# h_bridge_driver.net
KiCad netlist of a schematic drawn in EAGLE
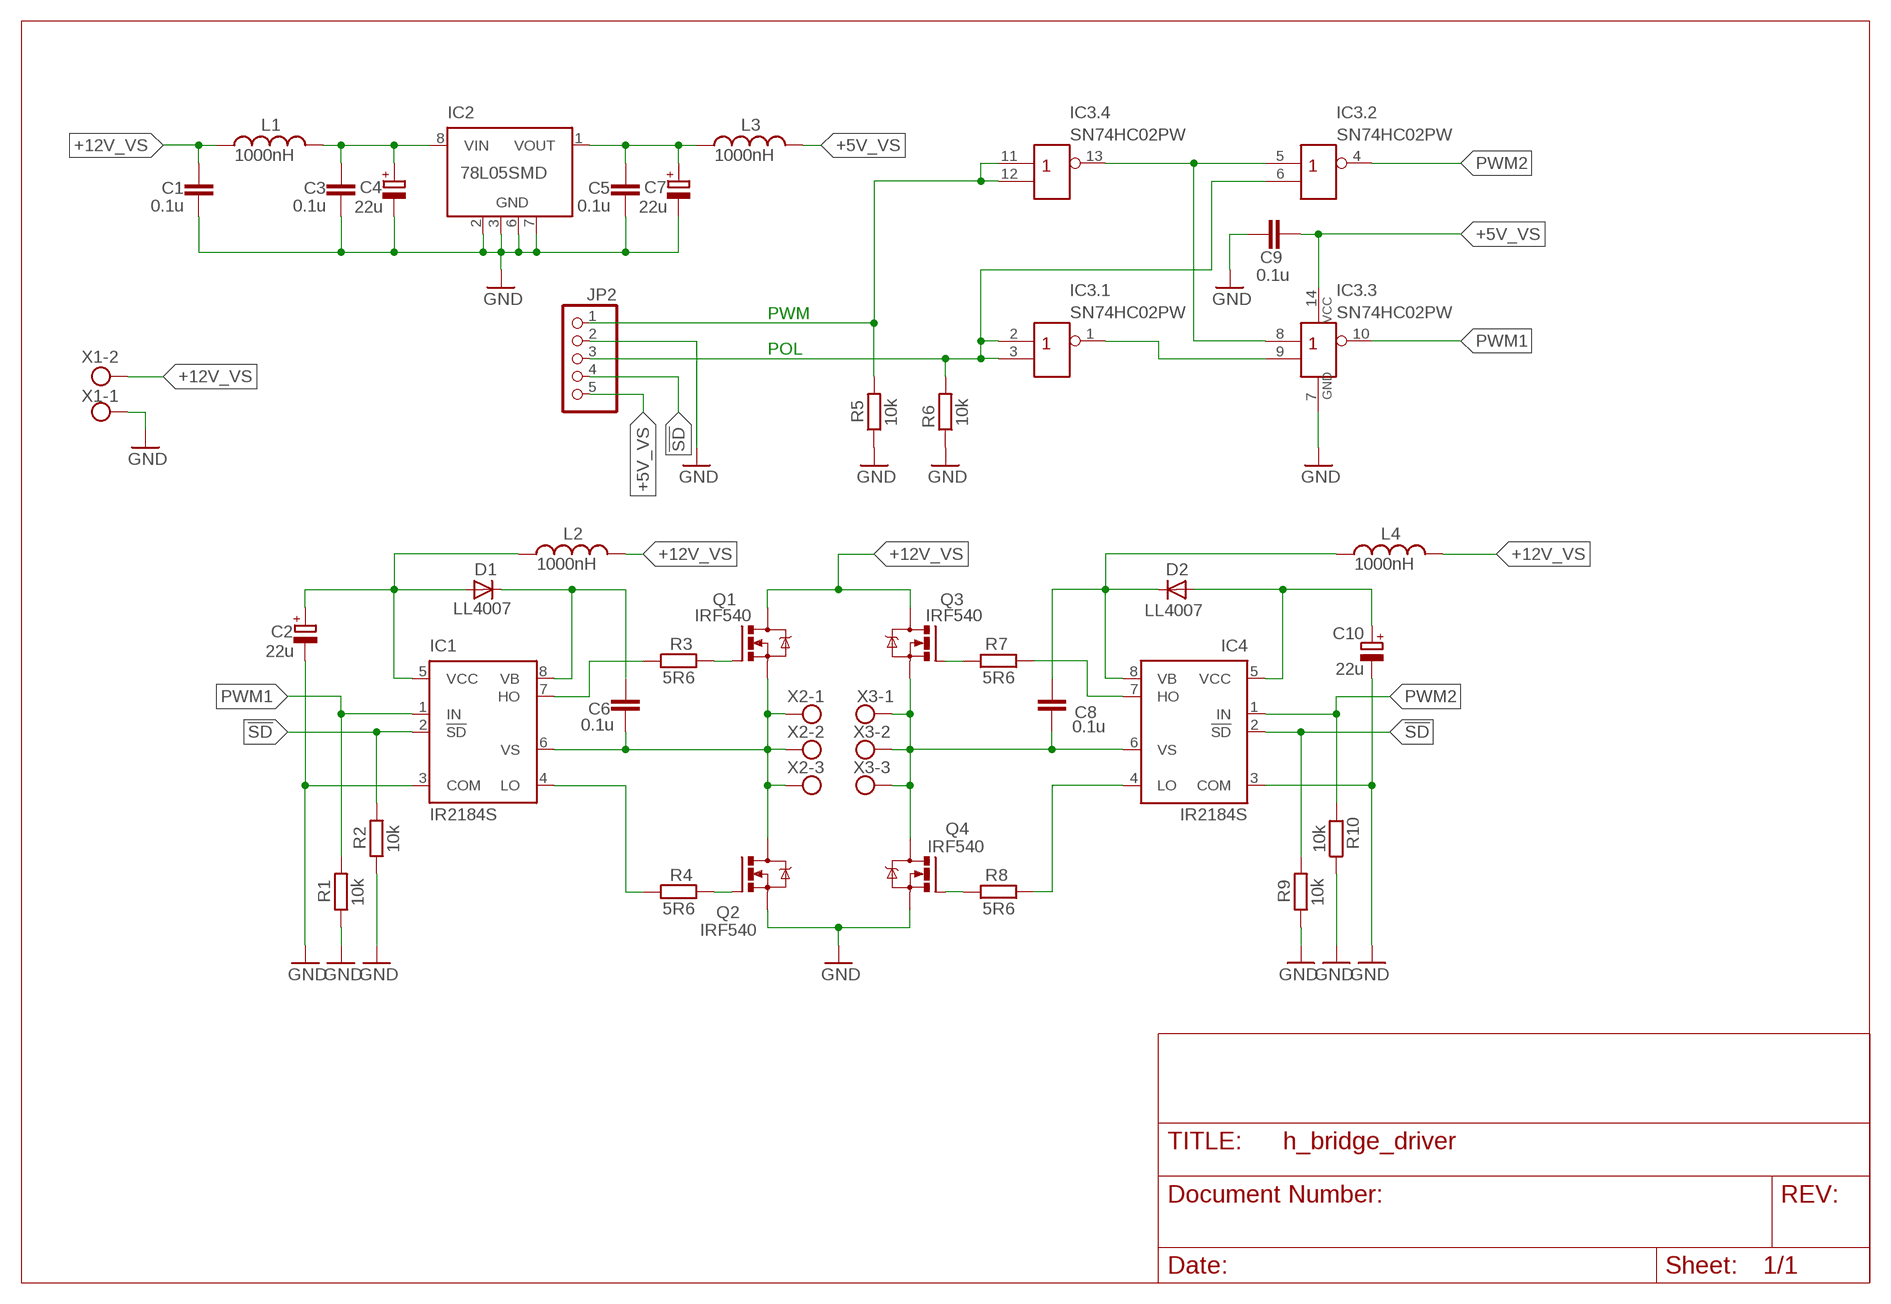
[diagram p0: schematic, sheet 1]

(export (version "E")
  (design (tool "Eeschema 10.0.6"))
  (components
    (comp (ref "C1")
      (value "0.1u")
      (footprint "eagle-import:C1206")
      (libsource (lib "eagle-import") (part "C-EUC1206"))
    )
    (comp (ref "C2")
      (value "22u")
      (footprint "eagle-import:SMC_C")
      (libsource (lib "eagle-import") (part "CPOL-EUSMCC"))
    )
    (comp (ref "C3")
      (value "0.1u")
      (footprint "eagle-import:C1206")
      (libsource (lib "eagle-import") (part "C-EUC1206"))
    )
    (comp (ref "C4")
      (value "22u")
      (footprint "eagle-import:SMC_C")
      (libsource (lib "eagle-import") (part "CPOL-EUSMCC"))
    )
    (comp (ref "C5")
      (value "0.1u")
      (footprint "eagle-import:C1206")
      (libsource (lib "eagle-import") (part "C-EUC1206"))
    )
    (comp (ref "C6")
      (value "0.1u")
      (footprint "eagle-import:C1206")
      (libsource (lib "eagle-import") (part "C-EUC1206"))
    )
    (comp (ref "C7")
      (value "22u")
      (footprint "eagle-import:SMC_C")
      (libsource (lib "eagle-import") (part "CPOL-EUSMCC"))
    )
    (comp (ref "C8")
      (value "0.1u")
      (footprint "eagle-import:C1206")
      (libsource (lib "eagle-import") (part "C-EUC1206"))
    )
    (comp (ref "C9")
      (value "0.1u")
      (footprint "eagle-import:C1206")
      (libsource (lib "eagle-import") (part "C-EUC1206"))
    )
    (comp (ref "C10")
      (value "22u")
      (footprint "eagle-import:SMC_C")
      (libsource (lib "eagle-import") (part "CPOL-EUSMCC"))
    )
    (comp (ref "D1")
      (value "LL4007")
      (footprint "eagle-import:MINIMELF")
      (libsource (lib "eagle-import") (part "DIODE-MINIMELF"))
    )
    (comp (ref "D2")
      (value "LL4007")
      (footprint "eagle-import:MINIMELF")
      (libsource (lib "eagle-import") (part "DIODE-MINIMELF"))
    )
    (comp (ref "IC1")
      (value "IR2184S")
      (footprint "eagle-import:SO08")
      (fields (field (name "MF") "INTERNATIONAL RECTIFIER(IR)") (field (name "MPN") "IR2184"))
      (libsource (lib "eagle-import") (part "IR2184S"))
    )
    (comp (ref "IC2")
      (value "78L05SMD")
      (footprint "eagle-import:SO08")
      (libsource (lib "eagle-import") (part "78LSMD05"))
    )
    (comp (ref "IC3")
      (value "SN74HC02PW")
      (footprint "eagle-import:SO14")
      (libsource (lib "eagle-import") (part "7402D"))
    )
    (comp (ref "IC4")
      (value "IR2184S")
      (footprint "eagle-import:SO08")
      (fields (field (name "MF") "INTERNATIONAL RECTIFIER(IR)") (field (name "MPN") "IR2184"))
      (libsource (lib "eagle-import") (part "IR2184S"))
    )
    (comp (ref "JP2")
      (value "PINHD-1X55X2MM")
      (footprint "eagle-import:1_05X2MM")
      (libsource (lib "eagle-import") (part "PINHD-1X55X2MM"))
    )
    (comp (ref "L1")
      (value "1000nH")
      (footprint "eagle-import:L1812")
      (libsource (lib "eagle-import") (part "L-USL1812"))
    )
    (comp (ref "L2")
      (value "1000nH")
      (footprint "eagle-import:L1812")
      (libsource (lib "eagle-import") (part "L-USL1812"))
    )
    (comp (ref "L3")
      (value "1000nH")
      (footprint "eagle-import:L1812")
      (libsource (lib "eagle-import") (part "L-USL1812"))
    )
    (comp (ref "L4")
      (value "1000nH")
      (footprint "eagle-import:L1812")
      (libsource (lib "eagle-import") (part "L-USL1812"))
    )
    (comp (ref "Q1")
      (value "IRF540")
      (footprint "eagle-import:TO220BV")
      (libsource (lib "eagle-import") (part "IRF540"))
    )
    (comp (ref "Q2")
      (value "IRF540")
      (footprint "eagle-import:TO220BV")
      (libsource (lib "eagle-import") (part "IRF540"))
    )
    (comp (ref "Q3")
      (value "IRF540")
      (footprint "eagle-import:TO220BV")
      (libsource (lib "eagle-import") (part "IRF540"))
    )
    (comp (ref "Q4")
      (value "IRF540")
      (footprint "eagle-import:TO220BV")
      (libsource (lib "eagle-import") (part "IRF540"))
    )
    (comp (ref "R1")
      (value "10k")
      (footprint "eagle-import:R0603")
      (libsource (lib "eagle-import") (part "R-EU_R0603"))
    )
    (comp (ref "R2")
      (value "10k")
      (footprint "eagle-import:R0603")
      (libsource (lib "eagle-import") (part "R-EU_R0603"))
    )
    (comp (ref "R3")
      (value "5R6")
      (footprint "eagle-import:R0603")
      (libsource (lib "eagle-import") (part "R-EU_R0603"))
    )
    (comp (ref "R4")
      (value "5R6")
      (footprint "eagle-import:R0603")
      (libsource (lib "eagle-import") (part "R-EU_R0603"))
    )
    (comp (ref "R5")
      (value "10k")
      (footprint "eagle-import:R0603")
      (libsource (lib "eagle-import") (part "R-EU_R0603"))
    )
    (comp (ref "R6")
      (value "10k")
      (footprint "eagle-import:R0603")
      (libsource (lib "eagle-import") (part "R-EU_R0603"))
    )
    (comp (ref "R7")
      (value "5R6")
      (footprint "eagle-import:R0603")
      (libsource (lib "eagle-import") (part "R-EU_R0603"))
    )
    (comp (ref "R8")
      (value "5R6")
      (footprint "eagle-import:R0603")
      (libsource (lib "eagle-import") (part "R-EU_R0603"))
    )
    (comp (ref "R9")
      (value "10k")
      (footprint "eagle-import:R0603")
      (libsource (lib "eagle-import") (part "R-EU_R0603"))
    )
    (comp (ref "R10")
      (value "10k")
      (footprint "eagle-import:R0603")
      (libsource (lib "eagle-import") (part "R-EU_R0603"))
    )
    (comp (ref "X1")
      (value "MKDSN1,5/2-5,08")
      (footprint "eagle-import:MKDSN1,5_2-5,08")
      (libsource (lib "eagle-import") (part "MKDSN1,5/2-5,08"))
    )
    (comp (ref "X2")
      (value "MKDSN1,5/3-5,08")
      (footprint "eagle-import:MKDSN1,5_3-5,08")
      (libsource (lib "eagle-import") (part "MKDSN1,5/3-5,08"))
    )
    (comp (ref "X3")
      (value "MKDSN1,5/3-5,08")
      (footprint "eagle-import:MKDSN1,5_3-5,08")
      (libsource (lib "eagle-import") (part "MKDSN1,5/3-5,08"))
    )
  )
  (nets
    (net (code "1") (name "+5V_VS") (class "Default")
      (node (ref "C9") (pin "1") (pinfunction "1_1") (pintype "passive"))
      (node (ref "IC3") (pin "14") (pinfunction "VCC_14") (pintype "power_in"))
      (node (ref "JP2") (pin "5") (pinfunction "5_5") (pintype "passive"))
      (node (ref "L3") (pin "2") (pinfunction "2_2") (pintype "passive"))
    )
    (net (code "2") (name "+12V_VS") (class "Default")
      (node (ref "C1") (pin "1") (pinfunction "1_1") (pintype "passive"))
      (node (ref "L1") (pin "1") (pinfunction "1_1") (pintype "passive"))
      (node (ref "L2") (pin "2") (pinfunction "2_2") (pintype "passive"))
      (node (ref "L4") (pin "2") (pinfunction "2_2") (pintype "passive"))
      (node (ref "Q1") (pin "D") (pinfunction "D_D") (pintype "passive"))
      (node (ref "Q3") (pin "D") (pinfunction "D_D") (pintype "passive"))
      (node (ref "X1") (pin "2") (pinfunction "KL_2") (pintype "passive"))
    )
    (net (code "3") (name "/~{SD}") (class "Default")
      (node (ref "IC1") (pin "2") (pinfunction "~{SD}_2") (pintype "input"))
      (node (ref "IC4") (pin "2") (pinfunction "~{SD}_2") (pintype "input"))
      (node (ref "JP2") (pin "4") (pinfunction "4_4") (pintype "passive"))
      (node (ref "R2") (pin "2") (pinfunction "2_2") (pintype "passive"))
      (node (ref "R9") (pin "2") (pinfunction "2_2") (pintype "passive"))
    )
    (net (code "4") (name "GND") (class "Default")
      (node (ref "C1") (pin "2") (pinfunction "2_2") (pintype "passive"))
      (node (ref "C10") (pin "-") (pinfunction "-_-") (pintype "passive"))
      (node (ref "C2") (pin "-") (pinfunction "-_-") (pintype "passive"))
      (node (ref "C3") (pin "2") (pinfunction "2_2") (pintype "passive"))
      (node (ref "C4") (pin "-") (pinfunction "-_-") (pintype "passive"))
      (node (ref "C5") (pin "2") (pinfunction "2_2") (pintype "passive"))
      (node (ref "C7") (pin "-") (pinfunction "-_-") (pintype "passive"))
      (node (ref "C9") (pin "2") (pinfunction "2_2") (pintype "passive"))
      (node (ref "IC1") (pin "3") (pinfunction "COM_3") (pintype "power_in"))
      (node (ref "IC2") (pin "2") (pinfunction "GND_2") (pintype "power_in"))
      (node (ref "IC2") (pin "3") (pinfunction "GND_3") (pintype "power_in"))
      (node (ref "IC2") (pin "6") (pinfunction "GND_6") (pintype "power_in"))
      (node (ref "IC2") (pin "7") (pinfunction "GND_7") (pintype "power_in"))
      (node (ref "IC3") (pin "7") (pinfunction "GND_7") (pintype "power_in"))
      (node (ref "IC4") (pin "3") (pinfunction "COM_3") (pintype "power_in"))
      (node (ref "JP2") (pin "2") (pinfunction "2_2") (pintype "passive"))
      (node (ref "Q2") (pin "S") (pinfunction "S_S") (pintype "passive"))
      (node (ref "Q4") (pin "S") (pinfunction "S_S") (pintype "passive"))
      (node (ref "R1") (pin "1") (pinfunction "1_1") (pintype "passive"))
      (node (ref "R10") (pin "1") (pinfunction "1_1") (pintype "passive"))
      (node (ref "R2") (pin "1") (pinfunction "1_1") (pintype "passive"))
      (node (ref "R5") (pin "1") (pinfunction "1_1") (pintype "passive"))
      (node (ref "R6") (pin "1") (pinfunction "1_1") (pintype "passive"))
      (node (ref "R9") (pin "1") (pinfunction "1_1") (pintype "passive"))
      (node (ref "X1") (pin "1") (pinfunction "KL_1") (pintype "passive"))
    )
    (net (code "5") (name "Net-(IC1-HO)") (class "Default")
      (node (ref "IC1") (pin "7") (pinfunction "HO_7") (pintype "passive"))
      (node (ref "R3") (pin "1") (pinfunction "1_1") (pintype "passive"))
    )
    (net (code "6") (name "Net-(IC1-LO)") (class "Default")
      (node (ref "IC1") (pin "4") (pinfunction "LO_4") (pintype "output"))
      (node (ref "R4") (pin "1") (pinfunction "1_1") (pintype "passive"))
    )
    (net (code "7") (name "Net-(IC1-VB)") (class "Default")
      (node (ref "C6") (pin "1") (pinfunction "1_1") (pintype "passive"))
      (node (ref "D1") (pin "C") (pinfunction "C_C") (pintype "passive"))
      (node (ref "IC1") (pin "8") (pinfunction "VB_8") (pintype "output"))
    )
    (net (code "8") (name "Net-(IC1-VCC)") (class "Default")
      (node (ref "C2") (pin "+") (pinfunction "+_+") (pintype "passive"))
      (node (ref "D1") (pin "A") (pinfunction "A_A") (pintype "passive"))
      (node (ref "IC1") (pin "5") (pinfunction "VCC_5") (pintype "power_in"))
      (node (ref "L2") (pin "1") (pinfunction "1_1") (pintype "passive"))
    )
    (net (code "9") (name "Net-(IC1-VS)") (class "Default")
      (node (ref "C6") (pin "2") (pinfunction "2_2") (pintype "passive"))
      (node (ref "IC1") (pin "6") (pinfunction "VS_6") (pintype "input"))
      (node (ref "Q1") (pin "S") (pinfunction "S_S") (pintype "passive"))
      (node (ref "Q2") (pin "D") (pinfunction "D_D") (pintype "passive"))
      (node (ref "X2") (pin "1") (pinfunction "KL_1") (pintype "passive"))
      (node (ref "X2") (pin "2") (pinfunction "KL_2") (pintype "passive"))
      (node (ref "X2") (pin "3") (pinfunction "KL_3") (pintype "passive"))
    )
    (net (code "10") (name "Net-(IC2A-VIN)") (class "Default")
      (node (ref "C3") (pin "1") (pinfunction "1_1") (pintype "passive"))
      (node (ref "C4") (pin "+") (pinfunction "+_+") (pintype "passive"))
      (node (ref "IC2") (pin "8") (pinfunction "VIN_8") (pintype "passive"))
      (node (ref "L1") (pin "2") (pinfunction "2_2") (pintype "passive"))
    )
    (net (code "11") (name "Net-(IC2A-VOUT)") (class "Default")
      (node (ref "C5") (pin "1") (pinfunction "1_1") (pintype "passive"))
      (node (ref "C7") (pin "+") (pinfunction "+_+") (pintype "passive"))
      (node (ref "IC2") (pin "1") (pinfunction "VOUT_1") (pintype "output"))
      (node (ref "L3") (pin "1") (pinfunction "1_1") (pintype "passive"))
    )
    (net (code "12") (name "Net-(IC3A-I0)") (class "Default")
      (node (ref "IC3") (pin "2") (pinfunction "I0_2") (pintype "input"))
      (node (ref "IC3") (pin "3") (pinfunction "I1_3") (pintype "input"))
      (node (ref "IC3") (pin "6") (pinfunction "I1_6") (pintype "input"))
      (node (ref "JP2") (pin "3") (pinfunction "3_3") (pintype "passive"))
      (node (ref "R6") (pin "2") (pinfunction "2_2") (pintype "passive"))
    )
    (net (code "13") (name "Net-(IC3A-O)") (class "Default")
      (node (ref "IC3") (pin "1") (pinfunction "O_1") (pintype "output"))
      (node (ref "IC3") (pin "9") (pinfunction "I1_9") (pintype "input"))
    )
    (net (code "14") (name "Net-(IC3B-I0)") (class "Default")
      (node (ref "IC3") (pin "13") (pinfunction "O_13") (pintype "output"))
      (node (ref "IC3") (pin "5") (pinfunction "I0_5") (pintype "input"))
      (node (ref "IC3") (pin "8") (pinfunction "I0_8") (pintype "input"))
    )
    (net (code "15") (name "Net-(IC3D-I0)") (class "Default")
      (node (ref "IC3") (pin "11") (pinfunction "I0_11") (pintype "input"))
      (node (ref "IC3") (pin "12") (pinfunction "I1_12") (pintype "input"))
      (node (ref "JP2") (pin "1") (pinfunction "1_1") (pintype "passive"))
      (node (ref "R5") (pin "2") (pinfunction "2_2") (pintype "passive"))
    )
    (net (code "16") (name "Net-(IC4-HO)") (class "Default")
      (node (ref "IC4") (pin "7") (pinfunction "HO_7") (pintype "passive"))
      (node (ref "R7") (pin "1") (pinfunction "1_1") (pintype "passive"))
    )
    (net (code "17") (name "Net-(IC4-LO)") (class "Default")
      (node (ref "IC4") (pin "4") (pinfunction "LO_4") (pintype "output"))
      (node (ref "R8") (pin "1") (pinfunction "1_1") (pintype "passive"))
    )
    (net (code "18") (name "Net-(IC4-VB)") (class "Default")
      (node (ref "C8") (pin "1") (pinfunction "1_1") (pintype "passive"))
      (node (ref "D2") (pin "C") (pinfunction "C_C") (pintype "passive"))
      (node (ref "IC4") (pin "8") (pinfunction "VB_8") (pintype "output"))
      (node (ref "L4") (pin "1") (pinfunction "1_1") (pintype "passive"))
    )
    (net (code "19") (name "Net-(IC4-VCC)") (class "Default")
      (node (ref "C10") (pin "+") (pinfunction "+_+") (pintype "passive"))
      (node (ref "D2") (pin "A") (pinfunction "A_A") (pintype "passive"))
      (node (ref "IC4") (pin "5") (pinfunction "VCC_5") (pintype "power_in"))
    )
    (net (code "20") (name "Net-(IC4-VS)") (class "Default")
      (node (ref "C8") (pin "2") (pinfunction "2_2") (pintype "passive"))
      (node (ref "IC4") (pin "6") (pinfunction "VS_6") (pintype "input"))
      (node (ref "Q3") (pin "S") (pinfunction "S_S") (pintype "passive"))
      (node (ref "Q4") (pin "D") (pinfunction "D_D") (pintype "passive"))
      (node (ref "X3") (pin "1") (pinfunction "KL_1") (pintype "passive"))
      (node (ref "X3") (pin "2") (pinfunction "KL_2") (pintype "passive"))
      (node (ref "X3") (pin "3") (pinfunction "KL_3") (pintype "passive"))
    )
    (net (code "21") (name "Net-(Q1-PadG)") (class "Default")
      (node (ref "Q1") (pin "G") (pinfunction "G_G") (pintype "passive"))
      (node (ref "R3") (pin "2") (pinfunction "2_2") (pintype "passive"))
    )
    (net (code "22") (name "Net-(Q2-PadG)") (class "Default")
      (node (ref "Q2") (pin "G") (pinfunction "G_G") (pintype "passive"))
      (node (ref "R4") (pin "2") (pinfunction "2_2") (pintype "passive"))
    )
    (net (code "23") (name "Net-(Q3-PadG)") (class "Default")
      (node (ref "Q3") (pin "G") (pinfunction "G_G") (pintype "passive"))
      (node (ref "R7") (pin "2") (pinfunction "2_2") (pintype "passive"))
    )
    (net (code "24") (name "Net-(Q4-PadG)") (class "Default")
      (node (ref "Q4") (pin "G") (pinfunction "G_G") (pintype "passive"))
      (node (ref "R8") (pin "2") (pinfunction "2_2") (pintype "passive"))
    )
    (net (code "25") (name "PWM1") (class "Default")
      (node (ref "IC1") (pin "1") (pinfunction "IN_1") (pintype "input"))
      (node (ref "IC3") (pin "10") (pinfunction "O_10") (pintype "output"))
      (node (ref "R1") (pin "2") (pinfunction "2_2") (pintype "passive"))
    )
    (net (code "26") (name "PWM2") (class "Default")
      (node (ref "IC3") (pin "4") (pinfunction "O_4") (pintype "output"))
      (node (ref "IC4") (pin "1") (pinfunction "IN_1") (pintype "input"))
      (node (ref "R10") (pin "2") (pinfunction "2_2") (pintype "passive"))
    )
  )
)
